# 16_key_i2c_pad_draft1.net
KiCad netlist of a schematic drawn in EAGLE
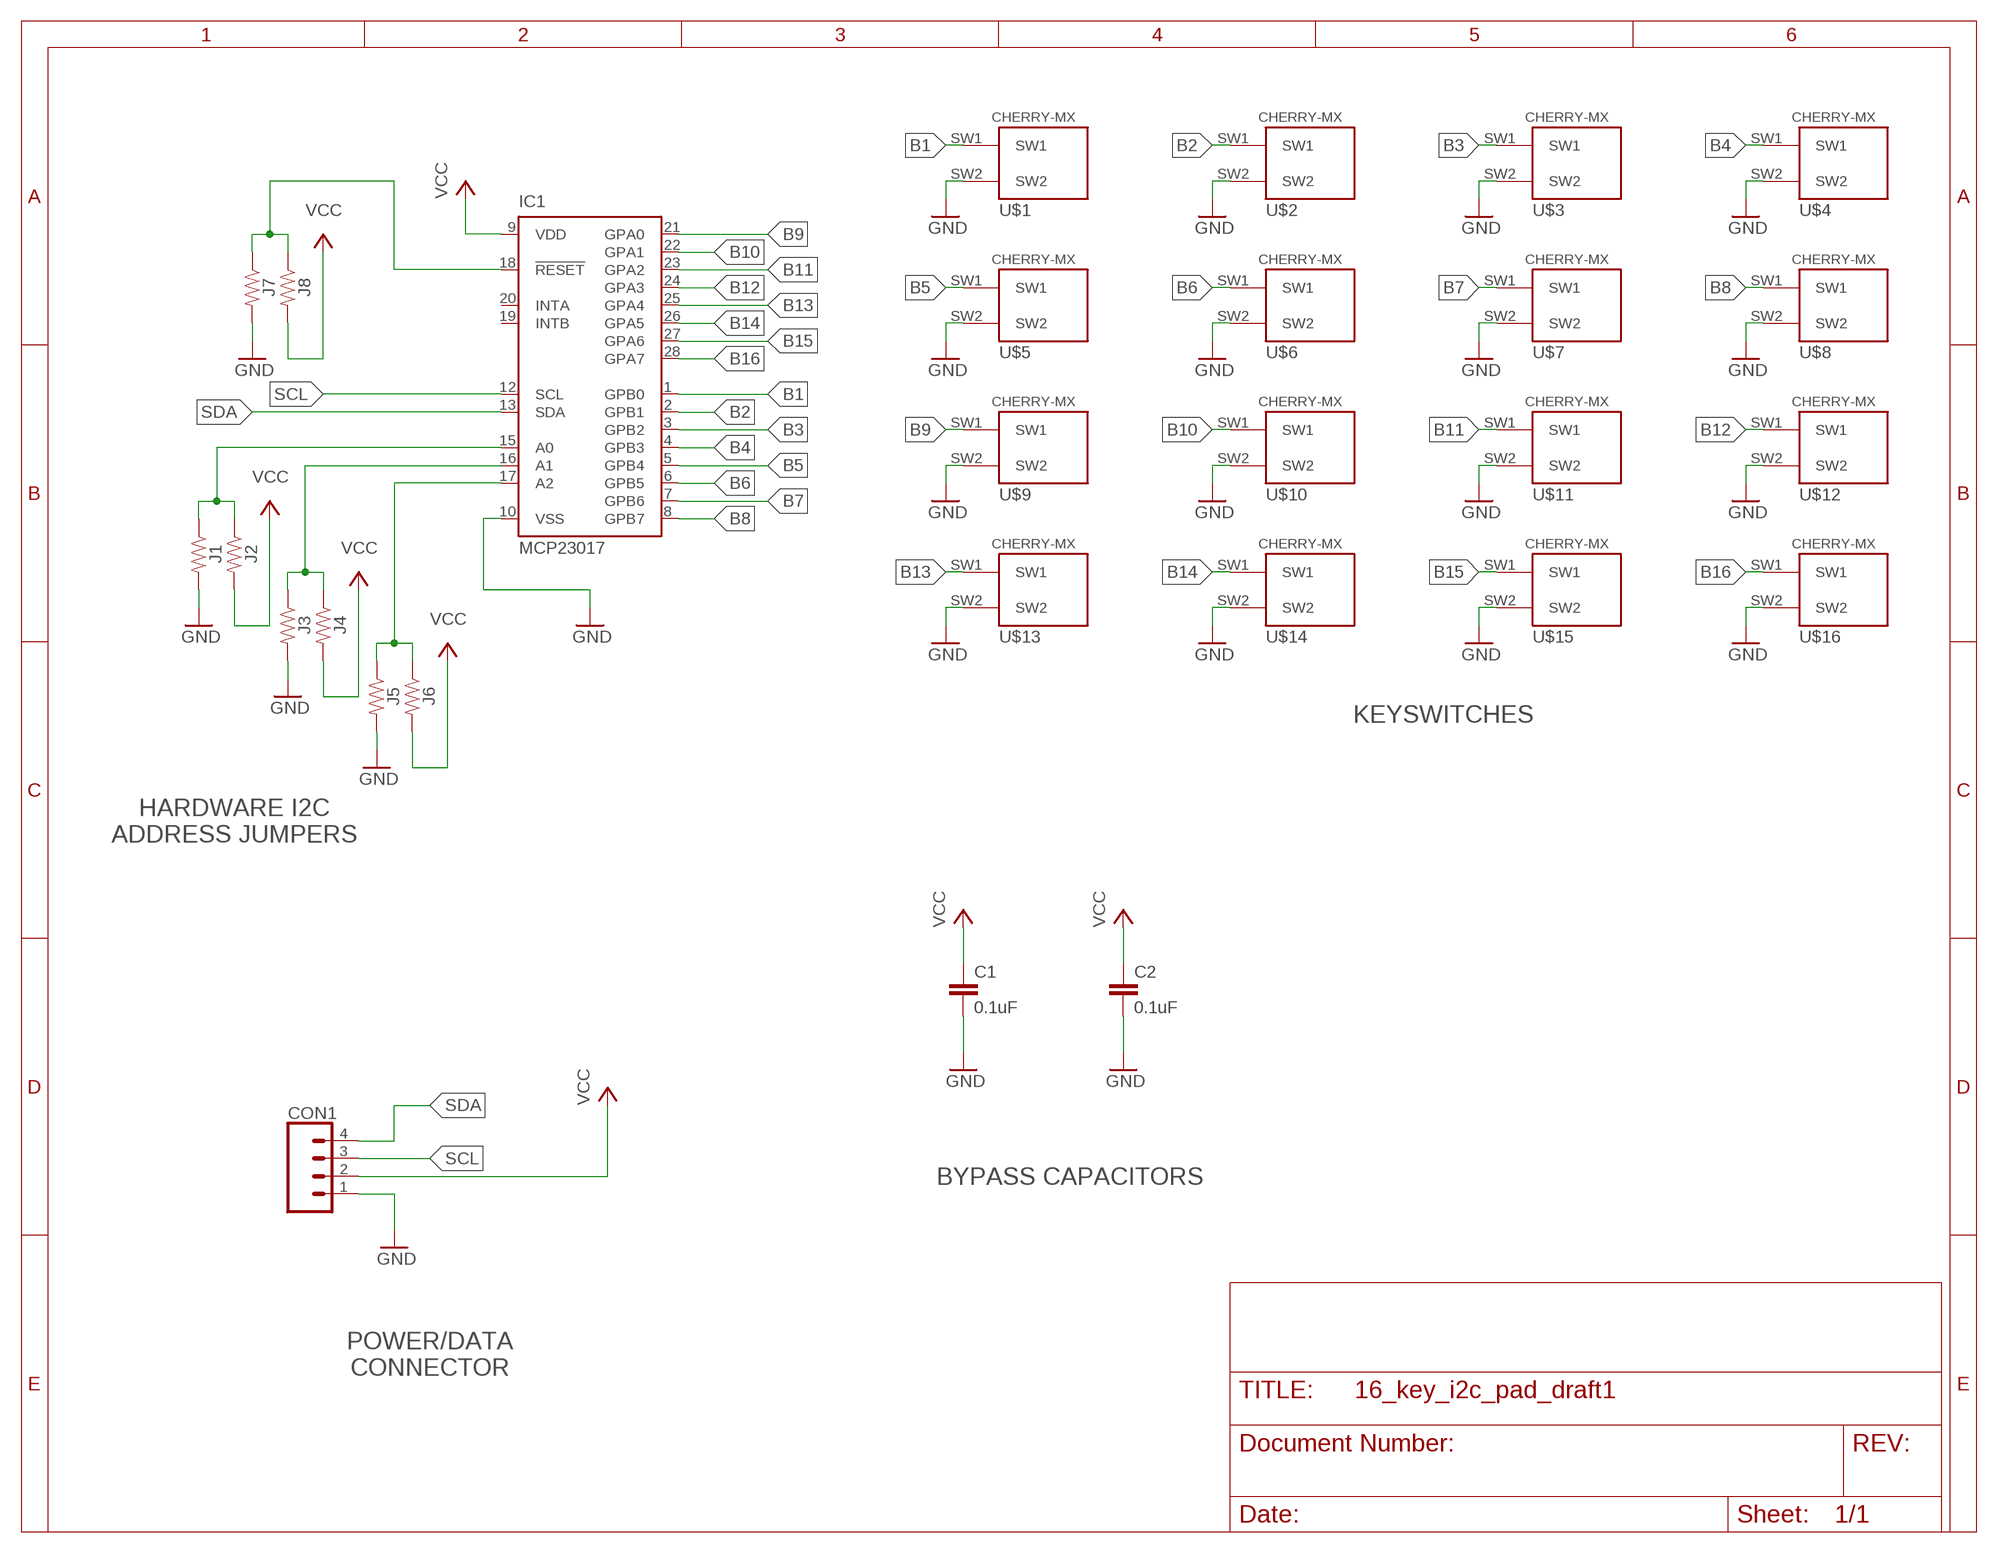
[diagram p0: schematic, sheet 1]

(export (version "E")
  (design (tool "Eeschema 10.0.6"))
  (components
    (comp (ref "C1")
      (value "0.1uF")
      (footprint "eagle-import:CAP-PTH-SMALL-KIT")
      (libsource (lib "eagle-import") (part "0.1UF-KIT-EZ-50V-20%"))
    )
    (comp (ref "C2")
      (value "0.1uF")
      (footprint "eagle-import:CAP-PTH-SMALL-KIT")
      (libsource (lib "eagle-import") (part "0.1UF-KIT-EZ-50V-20%"))
    )
    (comp (ref "CON1")
      (value "CONN_04")
      (footprint "eagle-import:1X04")
      (libsource (lib "eagle-import") (part "CONN_04"))
    )
    (comp (ref "IC1")
      (value "MCP23017")
      (footprint "eagle-import:DIL28-3")
      (fields (field (name "MF") "MICROCHIP") (field (name "MPN") "MCP23017-E/SP"))
      (libsource (lib "eagle-import") (part "MCP23017SP"))
    )
    (comp (ref "J1")
      (value "RESISTOR0805")
      (footprint "eagle-import:0805")
      (libsource (lib "eagle-import") (part "RESISTOR0805"))
    )
    (comp (ref "J2")
      (value "RESISTOR0805")
      (footprint "eagle-import:0805")
      (libsource (lib "eagle-import") (part "RESISTOR0805"))
    )
    (comp (ref "J3")
      (value "RESISTOR0805")
      (footprint "eagle-import:0805")
      (libsource (lib "eagle-import") (part "RESISTOR0805"))
    )
    (comp (ref "J4")
      (value "RESISTOR0805")
      (footprint "eagle-import:0805")
      (libsource (lib "eagle-import") (part "RESISTOR0805"))
    )
    (comp (ref "J5")
      (value "RESISTOR0805")
      (footprint "eagle-import:0805")
      (libsource (lib "eagle-import") (part "RESISTOR0805"))
    )
    (comp (ref "J6")
      (value "RESISTOR0805")
      (footprint "eagle-import:0805")
      (libsource (lib "eagle-import") (part "RESISTOR0805"))
    )
    (comp (ref "J7")
      (value "RESISTOR0805")
      (footprint "eagle-import:0805")
      (libsource (lib "eagle-import") (part "RESISTOR0805"))
    )
    (comp (ref "J8")
      (value "RESISTOR0805")
      (footprint "eagle-import:0805")
      (libsource (lib "eagle-import") (part "RESISTOR0805"))
    )
    (comp (ref "U$1")
      (value "CHERRY-MXSTANDARD")
      (footprint "eagle-import:CHERRY-MX")
      (libsource (lib "eagle-import") (part "CHERRY-MXSTANDARD"))
    )
    (comp (ref "U$2")
      (value "CHERRY-MXSTANDARD")
      (footprint "eagle-import:CHERRY-MX")
      (libsource (lib "eagle-import") (part "CHERRY-MXSTANDARD"))
    )
    (comp (ref "U$3")
      (value "CHERRY-MXSTANDARD")
      (footprint "eagle-import:CHERRY-MX")
      (libsource (lib "eagle-import") (part "CHERRY-MXSTANDARD"))
    )
    (comp (ref "U$4")
      (value "CHERRY-MXSTANDARD")
      (footprint "eagle-import:CHERRY-MX")
      (libsource (lib "eagle-import") (part "CHERRY-MXSTANDARD"))
    )
    (comp (ref "U$5")
      (value "CHERRY-MXSTANDARD")
      (footprint "eagle-import:CHERRY-MX")
      (libsource (lib "eagle-import") (part "CHERRY-MXSTANDARD"))
    )
    (comp (ref "U$6")
      (value "CHERRY-MXSTANDARD")
      (footprint "eagle-import:CHERRY-MX")
      (libsource (lib "eagle-import") (part "CHERRY-MXSTANDARD"))
    )
    (comp (ref "U$7")
      (value "CHERRY-MXSTANDARD")
      (footprint "eagle-import:CHERRY-MX")
      (libsource (lib "eagle-import") (part "CHERRY-MXSTANDARD"))
    )
    (comp (ref "U$8")
      (value "CHERRY-MXSTANDARD")
      (footprint "eagle-import:CHERRY-MX")
      (libsource (lib "eagle-import") (part "CHERRY-MXSTANDARD"))
    )
    (comp (ref "U$9")
      (value "CHERRY-MXSTANDARD")
      (footprint "eagle-import:CHERRY-MX")
      (libsource (lib "eagle-import") (part "CHERRY-MXSTANDARD"))
    )
    (comp (ref "U$10")
      (value "CHERRY-MXSTANDARD")
      (footprint "eagle-import:CHERRY-MX")
      (libsource (lib "eagle-import") (part "CHERRY-MXSTANDARD"))
    )
    (comp (ref "U$11")
      (value "CHERRY-MXSTANDARD")
      (footprint "eagle-import:CHERRY-MX")
      (libsource (lib "eagle-import") (part "CHERRY-MXSTANDARD"))
    )
    (comp (ref "U$12")
      (value "CHERRY-MXSTANDARD")
      (footprint "eagle-import:CHERRY-MX")
      (libsource (lib "eagle-import") (part "CHERRY-MXSTANDARD"))
    )
    (comp (ref "U$13")
      (value "CHERRY-MXSTANDARD")
      (footprint "eagle-import:CHERRY-MX")
      (libsource (lib "eagle-import") (part "CHERRY-MXSTANDARD"))
    )
    (comp (ref "U$14")
      (value "CHERRY-MXSTANDARD")
      (footprint "eagle-import:CHERRY-MX")
      (libsource (lib "eagle-import") (part "CHERRY-MXSTANDARD"))
    )
    (comp (ref "U$15")
      (value "CHERRY-MXSTANDARD")
      (footprint "eagle-import:CHERRY-MX")
      (libsource (lib "eagle-import") (part "CHERRY-MXSTANDARD"))
    )
    (comp (ref "U$16")
      (value "CHERRY-MXSTANDARD")
      (footprint "eagle-import:CHERRY-MX")
      (libsource (lib "eagle-import") (part "CHERRY-MXSTANDARD"))
    )
  )
  (nets
    (net (code "1") (name "B1") (class "Default")
      (node (ref "IC1") (pin "1") (pinfunction "GPB0_1") (pintype "bidirectional"))
      (node (ref "U$1") (pin "SW1") (pinfunction "SW1_SW1") (pintype "bidirectional"))
    )
    (net (code "2") (name "B2") (class "Default")
      (node (ref "IC1") (pin "2") (pinfunction "GPB1_2") (pintype "bidirectional"))
      (node (ref "U$2") (pin "SW1") (pinfunction "SW1_SW1") (pintype "bidirectional"))
    )
    (net (code "3") (name "B3") (class "Default")
      (node (ref "IC1") (pin "3") (pinfunction "GPB2_3") (pintype "bidirectional"))
      (node (ref "U$3") (pin "SW1") (pinfunction "SW1_SW1") (pintype "bidirectional"))
    )
    (net (code "4") (name "B4") (class "Default")
      (node (ref "IC1") (pin "4") (pinfunction "GPB3_4") (pintype "bidirectional"))
      (node (ref "U$4") (pin "SW1") (pinfunction "SW1_SW1") (pintype "bidirectional"))
    )
    (net (code "5") (name "B5") (class "Default")
      (node (ref "IC1") (pin "5") (pinfunction "GPB4_5") (pintype "bidirectional"))
      (node (ref "U$5") (pin "SW1") (pinfunction "SW1_SW1") (pintype "bidirectional"))
    )
    (net (code "6") (name "B6") (class "Default")
      (node (ref "IC1") (pin "6") (pinfunction "GPB5_6") (pintype "bidirectional"))
      (node (ref "U$6") (pin "SW1") (pinfunction "SW1_SW1") (pintype "bidirectional"))
    )
    (net (code "7") (name "B7") (class "Default")
      (node (ref "IC1") (pin "7") (pinfunction "GPB6_7") (pintype "bidirectional"))
      (node (ref "U$7") (pin "SW1") (pinfunction "SW1_SW1") (pintype "bidirectional"))
    )
    (net (code "8") (name "B8") (class "Default")
      (node (ref "IC1") (pin "8") (pinfunction "GPB7_8") (pintype "bidirectional"))
      (node (ref "U$8") (pin "SW1") (pinfunction "SW1_SW1") (pintype "bidirectional"))
    )
    (net (code "9") (name "B9") (class "Default")
      (node (ref "IC1") (pin "21") (pinfunction "GPA0_21") (pintype "bidirectional"))
      (node (ref "U$9") (pin "SW1") (pinfunction "SW1_SW1") (pintype "bidirectional"))
    )
    (net (code "10") (name "B10") (class "Default")
      (node (ref "IC1") (pin "22") (pinfunction "GPA1_22") (pintype "bidirectional"))
      (node (ref "U$10") (pin "SW1") (pinfunction "SW1_SW1") (pintype "bidirectional"))
    )
    (net (code "11") (name "B11") (class "Default")
      (node (ref "IC1") (pin "23") (pinfunction "GPA2_23") (pintype "bidirectional"))
      (node (ref "U$11") (pin "SW1") (pinfunction "SW1_SW1") (pintype "bidirectional"))
    )
    (net (code "12") (name "B12") (class "Default")
      (node (ref "IC1") (pin "24") (pinfunction "GPA3_24") (pintype "bidirectional"))
      (node (ref "U$12") (pin "SW1") (pinfunction "SW1_SW1") (pintype "bidirectional"))
    )
    (net (code "13") (name "B13") (class "Default")
      (node (ref "IC1") (pin "25") (pinfunction "GPA4_25") (pintype "bidirectional"))
      (node (ref "U$13") (pin "SW1") (pinfunction "SW1_SW1") (pintype "bidirectional"))
    )
    (net (code "14") (name "B14") (class "Default")
      (node (ref "IC1") (pin "26") (pinfunction "GPA5_26") (pintype "bidirectional"))
      (node (ref "U$14") (pin "SW1") (pinfunction "SW1_SW1") (pintype "bidirectional"))
    )
    (net (code "15") (name "B15") (class "Default")
      (node (ref "IC1") (pin "27") (pinfunction "GPA6_27") (pintype "bidirectional"))
      (node (ref "U$15") (pin "SW1") (pinfunction "SW1_SW1") (pintype "bidirectional"))
    )
    (net (code "16") (name "B16") (class "Default")
      (node (ref "IC1") (pin "28") (pinfunction "GPA7_28") (pintype "bidirectional"))
      (node (ref "U$16") (pin "SW1") (pinfunction "SW1_SW1") (pintype "bidirectional"))
    )
    (net (code "17") (name "GND") (class "Default")
      (node (ref "C1") (pin "2") (pinfunction "2_2") (pintype "passive"))
      (node (ref "C2") (pin "2") (pinfunction "2_2") (pintype "passive"))
      (node (ref "CON1") (pin "1") (pinfunction "1_1") (pintype "passive"))
      (node (ref "IC1") (pin "10") (pinfunction "VSS_10") (pintype "power_in"))
      (node (ref "J1") (pin "2") (pinfunction "2_2") (pintype "passive"))
      (node (ref "J3") (pin "2") (pinfunction "2_2") (pintype "passive"))
      (node (ref "J5") (pin "2") (pinfunction "2_2") (pintype "passive"))
      (node (ref "J7") (pin "2") (pinfunction "2_2") (pintype "passive"))
      (node (ref "U$1") (pin "SW2") (pinfunction "SW2_SW2") (pintype "bidirectional"))
      (node (ref "U$10") (pin "SW2") (pinfunction "SW2_SW2") (pintype "bidirectional"))
      (node (ref "U$11") (pin "SW2") (pinfunction "SW2_SW2") (pintype "bidirectional"))
      (node (ref "U$12") (pin "SW2") (pinfunction "SW2_SW2") (pintype "bidirectional"))
      (node (ref "U$13") (pin "SW2") (pinfunction "SW2_SW2") (pintype "bidirectional"))
      (node (ref "U$14") (pin "SW2") (pinfunction "SW2_SW2") (pintype "bidirectional"))
      (node (ref "U$15") (pin "SW2") (pinfunction "SW2_SW2") (pintype "bidirectional"))
      (node (ref "U$16") (pin "SW2") (pinfunction "SW2_SW2") (pintype "bidirectional"))
      (node (ref "U$2") (pin "SW2") (pinfunction "SW2_SW2") (pintype "bidirectional"))
      (node (ref "U$3") (pin "SW2") (pinfunction "SW2_SW2") (pintype "bidirectional"))
      (node (ref "U$4") (pin "SW2") (pinfunction "SW2_SW2") (pintype "bidirectional"))
      (node (ref "U$5") (pin "SW2") (pinfunction "SW2_SW2") (pintype "bidirectional"))
      (node (ref "U$6") (pin "SW2") (pinfunction "SW2_SW2") (pintype "bidirectional"))
      (node (ref "U$7") (pin "SW2") (pinfunction "SW2_SW2") (pintype "bidirectional"))
      (node (ref "U$8") (pin "SW2") (pinfunction "SW2_SW2") (pintype "bidirectional"))
      (node (ref "U$9") (pin "SW2") (pinfunction "SW2_SW2") (pintype "bidirectional"))
    )
    (net (code "18") (name "Net-(IC1-A0)") (class "Default")
      (node (ref "IC1") (pin "15") (pinfunction "A0_15") (pintype "input"))
      (node (ref "J1") (pin "1") (pinfunction "1_1") (pintype "passive"))
      (node (ref "J2") (pin "1") (pinfunction "1_1") (pintype "passive"))
    )
    (net (code "19") (name "Net-(IC1-A1)") (class "Default")
      (node (ref "IC1") (pin "16") (pinfunction "A1_16") (pintype "input"))
      (node (ref "J3") (pin "1") (pinfunction "1_1") (pintype "passive"))
      (node (ref "J4") (pin "1") (pinfunction "1_1") (pintype "passive"))
    )
    (net (code "20") (name "Net-(IC1-A2)") (class "Default")
      (node (ref "IC1") (pin "17") (pinfunction "A2_17") (pintype "input"))
      (node (ref "J5") (pin "1") (pinfunction "1_1") (pintype "passive"))
      (node (ref "J6") (pin "1") (pinfunction "1_1") (pintype "passive"))
    )
    (net (code "21") (name "Net-(IC1-~{RESET})") (class "Default")
      (node (ref "IC1") (pin "18") (pinfunction "~{RESET}_18") (pintype "input"))
      (node (ref "J7") (pin "1") (pinfunction "1_1") (pintype "passive"))
      (node (ref "J8") (pin "1") (pinfunction "1_1") (pintype "passive"))
    )
    (net (code "22") (name "SCL") (class "Default")
      (node (ref "CON1") (pin "3") (pinfunction "3_3") (pintype "passive"))
      (node (ref "IC1") (pin "12") (pinfunction "SCL_12") (pintype "input"))
    )
    (net (code "23") (name "SDA") (class "Default")
      (node (ref "CON1") (pin "4") (pinfunction "4_4") (pintype "passive"))
      (node (ref "IC1") (pin "13") (pinfunction "SDA_13") (pintype "bidirectional"))
    )
    (net (code "24") (name "VCC") (class "Default")
      (node (ref "C1") (pin "1") (pinfunction "1_1") (pintype "passive"))
      (node (ref "C2") (pin "1") (pinfunction "1_1") (pintype "passive"))
      (node (ref "CON1") (pin "2") (pinfunction "2_2") (pintype "passive"))
      (node (ref "IC1") (pin "9") (pinfunction "VDD_9") (pintype "power_in"))
      (node (ref "J2") (pin "2") (pinfunction "2_2") (pintype "passive"))
      (node (ref "J4") (pin "2") (pinfunction "2_2") (pintype "passive"))
      (node (ref "J6") (pin "2") (pinfunction "2_2") (pintype "passive"))
      (node (ref "J8") (pin "2") (pinfunction "2_2") (pintype "passive"))
    )
    (net (code "25") (name "unconnected-(IC1-INTA-Pad20)") (class "Default")
      (node (ref "IC1") (pin "20") (pinfunction "INTA_20") (pintype "output"))
    )
    (net (code "26") (name "unconnected-(IC1-INTB-Pad19)") (class "Default")
      (node (ref "IC1") (pin "19") (pinfunction "INTB_19") (pintype "output"))
    )
  )
)
